# SW1106_100W_C_SH1.net
KiCad netlist of a schematic drawn in Altium Designer
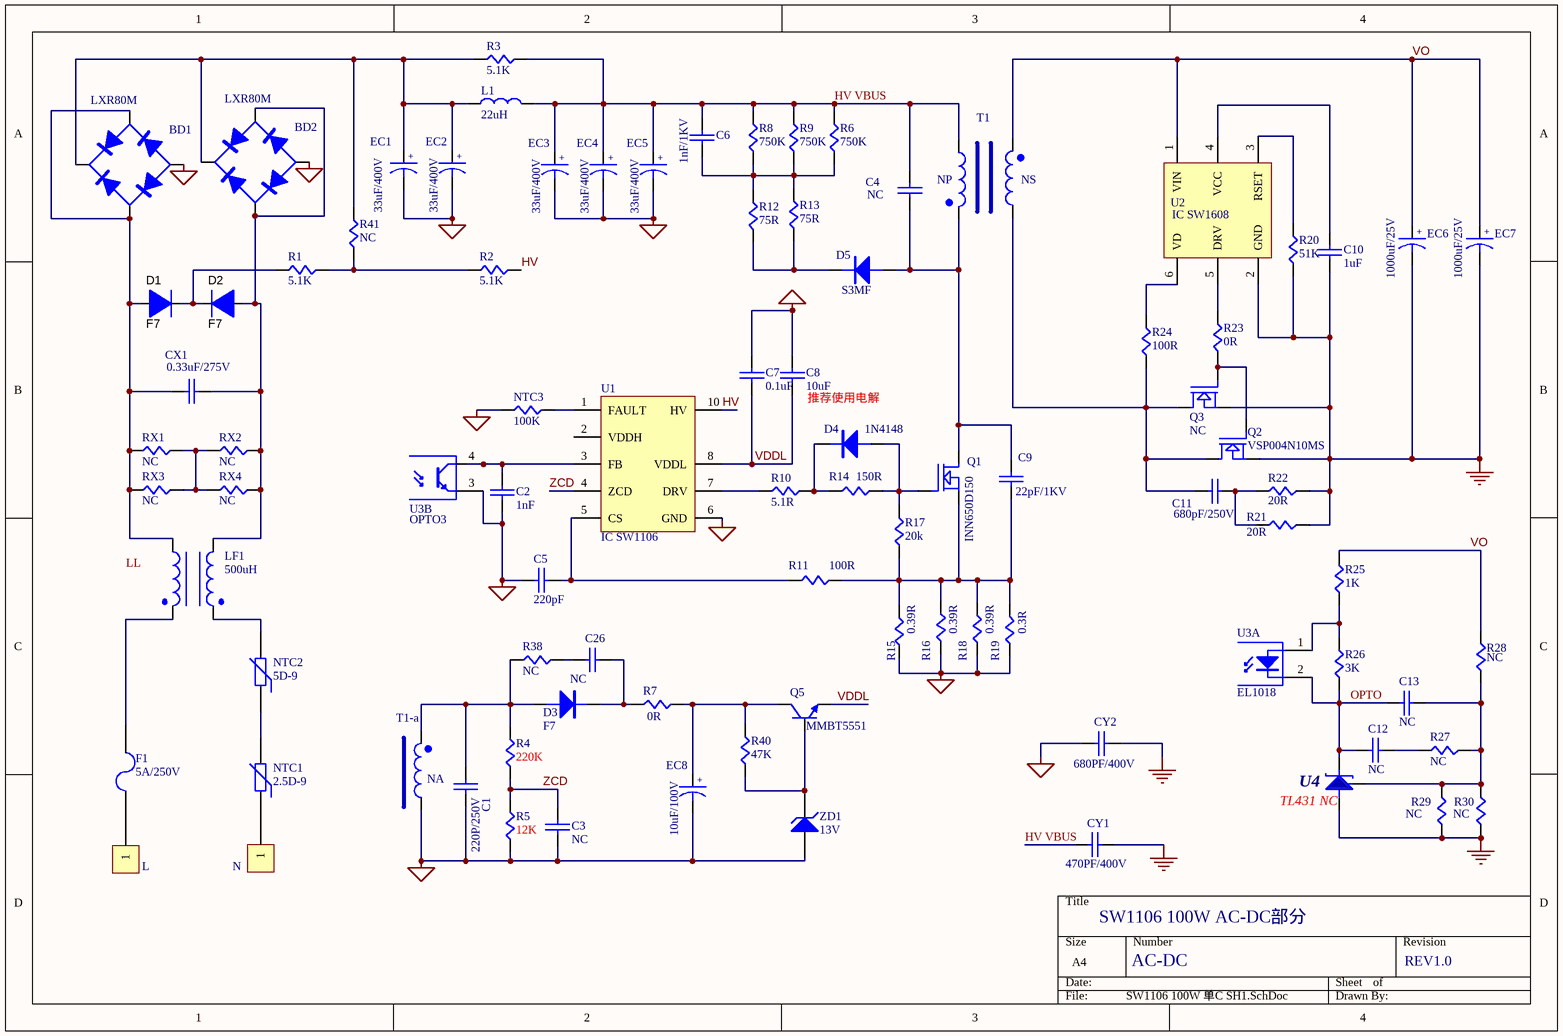
[diagram p0: SW1106 100W 单C SH1.SchDoc]

(export (version "E")
  (design (tool "Eeschema 10.0.6"))
  (components
    (comp (ref "BD1")
      (value "LXR80M")
      (footprint "BD-MBSL")
      (description "Diode")
      (libsource (lib "SCH-new") (part "BRIDGE"))
    )
    (comp (ref "BD2")
      (value "LXR80M")
      (footprint "BD-MBSL")
      (description "Diode")
      (libsource (lib "SCH-new") (part "BRIDGE"))
    )
    (comp (ref "C1")
      (value "220P/250V")
      (footprint "0603-C")
      (description "Capacitor")
      (libsource (lib "Backup of wdm_protel_libsch") (part "CAP"))
    )
    (comp (ref "C2")
      (value "1nF")
      (footprint "0603-C")
      (description "Capacitor")
      (libsource (lib "Backup of wdm_protel_libsch") (part "CAP"))
    )
    (comp (ref "C3")
      (value "NC")
      (footprint "0603-C")
      (description "Capacitor")
      (libsource (lib "Backup of wdm_protel_libsch") (part "CAP"))
    )
    (comp (ref "C4")
      (value "NC")
      (footprint "0805_C")
      (description "Capacitor")
      (libsource (lib "Backup of SC_ACDC_AD_libsch") (part "CAP"))
    )
    (comp (ref "C5")
      (value "220pF")
      (footprint "0603-C")
      (description "Capacitor")
      (libsource (lib "Backup of wdm_protel_libsch") (part "CAP"))
    )
    (comp (ref "C6")
      (value "1nF/1KV")
      (footprint "1206-C")
      (description "Capacitor")
      (libsource (lib "Backup of SC_ACDC_AD_libsch") (part "CAP"))
    )
    (comp (ref "C7")
      (value "0.1uF")
      (footprint "0805_C")
      (description "Capacitor")
      (libsource (lib "Backup of SC_ACDC_AD_libsch") (part "CAP"))
    )
    (comp (ref "C8")
      (value "10uF")
      (footprint "1206-C")
      (description "Capacitor")
      (libsource (lib "Backup of SC_ACDC_AD_libsch") (part "CAP"))
    )
    (comp (ref "C9")
      (value "22pF/1KV")
      (footprint "1206-C")
      (description "Capacitor")
      (libsource (lib "Backup of SC_ACDC_AD_libsch") (part "CAP"))
    )
    (comp (ref "C10")
      (value "1uF")
      (footprint "0603-C")
      (description "Capacitor")
      (libsource (lib "Backup of SC_ACDC_AD_libsch") (part "CAP"))
    )
    (comp (ref "C11")
      (value "680pF/250V")
      (footprint "0805_C")
      (description "Capacitor")
      (libsource (lib "Backup of SC_ACDC_AD_libsch") (part "CAP"))
    )
    (comp (ref "C12")
      (value "NC")
      (footprint "0603")
      (description "Capacitor")
      (libsource (lib "Backup of SC_ACDC_AD_libsch") (part "CAP"))
    )
    (comp (ref "C13")
      (value "NC")
      (footprint "0603")
      (description "Capacitor")
      (libsource (lib "Backup of SC_ACDC_AD_libsch") (part "CAP"))
    )
    (comp (ref "C26")
      (value "NC")
      (footprint "0805_C")
      (description "Capacitor")
      (libsource (lib "Backup of SC_ACDC_AD_libsch") (part "CAP"))
    )
    (comp (ref "CX1")
      (value "0.33uF/275V")
      (footprint "X-10-CAP - 3")
      (description "安规电容CHAMPION  X2\r\n尺寸：10X5X11mm（长X宽X高）\r\n脚距：7.5mm")
      (libsource (lib "xiaodenrui") (part "C"))
    )
    (comp (ref "CY1")
      (value "470PF/400V")
      (footprint "Y-SMD")
      (description "Capacitor")
      (libsource (lib "Backup of SC_ACDC_AD_libsch") (part "CAP"))
    )
    (comp (ref "CY2")
      (value "680PF/400V")
      (footprint "Y-SMD")
      (description "Capacitor")
      (libsource (lib "Backup of SC_ACDC_AD_libsch") (part "CAP"))
    )
    (comp (ref "D1")
      (value "F7")
      (footprint "SOD-123H")
      (description "1N4148 SOD323(0805)")
      (libsource (lib "*") (part "CSFMT108-HF"))
    )
    (comp (ref "D2")
      (value "F7")
      (footprint "SOD-123H")
      (description "1N4148 SOD323(0805)")
      (libsource (lib "*") (part "CSFMT108-HF"))
    )
    (comp (ref "D3")
      (value "F7")
      (footprint "SOD-123F")
      (description "Diode")
      (libsource (lib "Backup of wdm_protel_libsch") (part "DIODE_1"))
    )
    (comp (ref "D4")
      (value "1N4148")
      (footprint "SOD-323")
      (description "Diode")
      (libsource (lib "Backup of wdm_protel_libsch") (part "DIODE_1"))
    )
    (comp (ref "D5")
      (value "S3MF")
      (footprint "DIODE-S2MB")
      (description "Diode")
      (libsource (lib "Backup of SC_ACDC_AD_libsch") (part "DIODE"))
    )
    (comp (ref "EC1")
      (value "33uF/400V")
      (footprint "CD-8/3.5")
      (description "Capacitor")
      (libsource (lib "Backup of SC_ACDC_AD_libsch") (part "CAPACITOR POL"))
    )
    (comp (ref "EC2")
      (value "33uF/400V")
      (footprint "CD-8/3.5")
      (description "Capacitor")
      (libsource (lib "Backup of SC_ACDC_AD_libsch") (part "CAPACITOR POL"))
    )
    (comp (ref "EC3")
      (value "33uF/400V")
      (footprint "CD-8/3.5")
      (description "Capacitor")
      (libsource (lib "Backup of SC_ACDC_AD_libsch") (part "CAPACITOR POL"))
    )
    (comp (ref "EC4")
      (value "33uF/400V")
      (footprint "CD-8/3.5")
      (description "Capacitor")
      (libsource (lib "Backup of SC_ACDC_AD_libsch") (part "CAPACITOR POL"))
    )
    (comp (ref "EC5")
      (value "33uF/400V")
      (footprint "CD-8/3.5")
      (description "Capacitor")
      (libsource (lib "Backup of SC_ACDC_AD_libsch") (part "CAPACITOR POL"))
    )
    (comp (ref "EC6")
      (value "1000uF/25V")
      (footprint "CD-6.3/2.3")
      (description "Capacitor")
      (libsource (lib "Backup of SC_ACDC_AD_libsch") (part "CAPACITOR POL"))
    )
    (comp (ref "EC7")
      (value "1000uF/25V")
      (footprint "CD-6.3/2.3")
      (description "Capacitor")
      (libsource (lib "Backup of SC_ACDC_AD_libsch") (part "CAPACITOR POL"))
    )
    (comp (ref "EC8")
      (value "10uF/100V")
      (footprint "CD-8/3.5")
      (description "Capacitor")
      (libsource (lib "Backup of SC_ACDC_AD_libsch") (part "CAPACITOR POL"))
    )
    (comp (ref "F1")
      (value "5A/250V")
      (footprint "F-8.5*4-P5")
      (description "Fuse")
      (libsource (lib "Backup of SC_ACDC_AD_libsch") (part "FUSE"))
    )
    (comp (ref "L")
      (value "L")
      (footprint "焊盘1.5mm")
      (description "Connector")
      (libsource (lib "Backup of SC_ACDC_AD_libsch") (part "CON1"))
    )
    (comp (ref "L1")
      (value "22uH")
      (footprint "LF-D8-P5")
      (description "inductor")
      (libsource (lib "Backup of SC_ACDC_AD_libsch") (part "L1"))
    )
    (comp (ref "LF1")
      (value "500uH")
      (footprint "LF-9X3.2")
      (description "16.2uH")
      (libsource (lib "SCH-new") (part "LF-4-7"))
    )
    (comp (ref "N")
      (value "N")
      (footprint "焊盘1.5mm")
      (description "Connector")
      (libsource (lib "Backup of SC_ACDC_AD_libsch") (part "CON1"))
    )
    (comp (ref "NS") (value "~") (libsource (lib "*") (part "INDUCTOR")))
    (comp (ref "NTC1")
      (value "2.5D-9")
      (footprint "5D9")
      (description "Varistor (Voltage-Sensitive Resistor)")
      (fields (field (name "PUBLISHER") "Altium Limited"))
      (libsource (lib "Miscellaneous Devices") (part "Res Varistor"))
    )
    (comp (ref "NTC2")
      (value "5D-9")
      (footprint "5D9")
      (description "Varistor (Voltage-Sensitive Resistor)")
      (fields (field (name "PUBLISHER") "Altium Limited"))
      (libsource (lib "Miscellaneous Devices") (part "Res Varistor"))
    )
    (comp (ref "NTC3")
      (value "100K")
      (footprint "0603-R")
      (libsource (lib "Backup of SC_ACDC_AD_libsch") (part "RES2"))
    )
    (comp (ref "Q1")
      (value "INN650D150")
      (footprint "TO220-GDS")
      (description "SFS06R02UG 60V/3.2mR PDFN5*6 东微")
      (libsource (lib "zoujianSch-AD20-1.0") (part "NMOSFET (Z)"))
    )
    (comp (ref "Q2")
      (value "VSP004N10MS")
      (footprint "TO220-GDS")
      (description "SFS06R02UG 60V/3.2mR PDFN5*6 东微")
      (libsource (lib "zoujianSch-AD20-1.0") (part "NMOSFET (Z)"))
    )
    (comp (ref "Q3")
      (value "NC")
      (footprint "TO220-GDS")
      (description "SFS06R02UG 60V/3.2mR PDFN5*6 东微")
      (libsource (lib "zoujianSch-AD20-1.0") (part "NMOSFET (Z)"))
    )
    (comp (ref "Q5")
      (value "MMBT5551")
      (footprint "SOT-23")
      (description "NPN 三极管")
      (libsource (lib "元件库2020-10-13") (part "NPN"))
    )
    (comp (ref "R1")
      (value "5.1K")
      (footprint "1206-R")
      (libsource (lib "Backup of SC_ACDC_AD_libsch") (part "RES2"))
    )
    (comp (ref "R2")
      (value "5.1K")
      (footprint "1206-R")
      (libsource (lib "Backup of SC_ACDC_AD_libsch") (part "RES2"))
    )
    (comp (ref "R3")
      (value "5.1K")
      (footprint "1206-R")
      (libsource (lib "Backup of SC_ACDC_AD_libsch") (part "RES2"))
    )
    (comp (ref "R4")
      (value "220K")
      (footprint "0603-R")
      (libsource (lib "Backup of SC_ACDC_AD_libsch") (part "RES2"))
    )
    (comp (ref "R5")
      (value "12K")
      (footprint "0603-R")
      (libsource (lib "Backup of SC_ACDC_AD_libsch") (part "RES2"))
    )
    (comp (ref "R6")
      (value "750K")
      (footprint "1206-R")
      (libsource (lib "Backup of SC_ACDC_AD_libsch") (part "RES2"))
    )
    (comp (ref "R7")
      (value "0R")
      (footprint "0805-R")
      (libsource (lib "Backup of SC_ACDC_AD_libsch") (part "RES2"))
    )
    (comp (ref "R8")
      (value "750K")
      (footprint "1206-R")
      (libsource (lib "Backup of SC_ACDC_AD_libsch") (part "RES2"))
    )
    (comp (ref "R9")
      (value "750K")
      (footprint "1206-R")
      (libsource (lib "Backup of SC_ACDC_AD_libsch") (part "RES2"))
    )
    (comp (ref "R10")
      (value "5.1R")
      (footprint "0603-R")
      (libsource (lib "Backup of SC_ACDC_AD_libsch") (part "RES2"))
    )
    (comp (ref "R11")
      (value "100R")
      (footprint "0603-R")
      (libsource (lib "Backup of SC_ACDC_AD_libsch") (part "RES2"))
    )
    (comp (ref "R12")
      (value "75R")
      (footprint "1206-R")
      (libsource (lib "Backup of SC_ACDC_AD_libsch") (part "RES2"))
    )
    (comp (ref "R13")
      (value "75R")
      (footprint "1206-R")
      (libsource (lib "Backup of SC_ACDC_AD_libsch") (part "RES2"))
    )
    (comp (ref "R14")
      (value "150R")
      (footprint "0603-R")
      (libsource (lib "Backup of SC_ACDC_AD_libsch") (part "RES2"))
    )
    (comp (ref "R15")
      (value "0.39R")
      (footprint "1206-R")
      (libsource (lib "Backup of SC_ACDC_AD_libsch") (part "RES2"))
    )
    (comp (ref "R16")
      (value "0.39R")
      (footprint "1206-R")
      (libsource (lib "Backup of SC_ACDC_AD_libsch") (part "RES2"))
    )
    (comp (ref "R17")
      (value "20k")
      (footprint "0603-R")
      (libsource (lib "Backup of SC_ACDC_AD_libsch") (part "RES2"))
    )
    (comp (ref "R18")
      (value "0.39R")
      (footprint "1206-R")
      (libsource (lib "Backup of SC_ACDC_AD_libsch") (part "RES2"))
    )
    (comp (ref "R19")
      (value "0.3R")
      (footprint "1206-R")
      (libsource (lib "Backup of SC_ACDC_AD_libsch") (part "RES2"))
    )
    (comp (ref "R20")
      (value "51K")
      (footprint "0603-R")
      (libsource (lib "Backup of SC_ACDC_AD_libsch") (part "RES2"))
    )
    (comp (ref "R21")
      (value "20R")
      (footprint "0805-R")
      (libsource (lib "Backup of SC_ACDC_AD_libsch") (part "RES2"))
    )
    (comp (ref "R22")
      (value "20R")
      (footprint "0805-R")
      (libsource (lib "Backup of SC_ACDC_AD_libsch") (part "RES2"))
    )
    (comp (ref "R23")
      (value "0R")
      (footprint "0603-R")
      (libsource (lib "Backup of SC_ACDC_AD_libsch") (part "RES2"))
    )
    (comp (ref "R24")
      (value "100R")
      (footprint "0603-R")
      (libsource (lib "Backup of SC_ACDC_AD_libsch") (part "RES2"))
    )
    (comp (ref "R25")
      (value "1K")
      (footprint "0603-R")
      (libsource (lib "Backup of SC_ACDC_AD_libsch") (part "RES2"))
    )
    (comp (ref "R26")
      (value "3K")
      (footprint "0603-R")
      (libsource (lib "Backup of SC_ACDC_AD_libsch") (part "RES2"))
    )
    (comp (ref "R27")
      (value "NC")
      (footprint "0603")
      (libsource (lib "Backup of SC_ACDC_AD_libsch") (part "RES2"))
    )
    (comp (ref "R28")
      (value "NC")
      (footprint "0603")
      (libsource (lib "Backup of SC_ACDC_AD_libsch") (part "RES2"))
    )
    (comp (ref "R29")
      (value "NC")
      (footprint "0603")
      (libsource (lib "Backup of SC_ACDC_AD_libsch") (part "RES2"))
    )
    (comp (ref "R30")
      (value "NC")
      (footprint "0603")
      (libsource (lib "Backup of SC_ACDC_AD_libsch") (part "RES2"))
    )
    (comp (ref "R38")
      (value "NC")
      (footprint "0603-R")
      (libsource (lib "Backup of SC_ACDC_AD_libsch") (part "RES2"))
    )
    (comp (ref "R40")
      (value "47K")
      (footprint "0805-R")
      (libsource (lib "Backup of SC_ACDC_AD_libsch") (part "RES2"))
    )
    (comp (ref "R41")
      (value "NC")
      (footprint "1206-R")
      (libsource (lib "Backup of SC_ACDC_AD_libsch") (part "RES2"))
    )
    (comp (ref "RX1")
      (value "NC")
      (footprint "1206-R")
      (libsource (lib "Backup of SC_ACDC_AD_libsch") (part "RES2"))
    )
    (comp (ref "RX2")
      (value "NC")
      (footprint "1206-R")
      (libsource (lib "Backup of SC_ACDC_AD_libsch") (part "RES2"))
    )
    (comp (ref "RX3")
      (value "NC")
      (footprint "1206-R")
      (libsource (lib "Backup of SC_ACDC_AD_libsch") (part "RES2"))
    )
    (comp (ref "RX4")
      (value "NC")
      (footprint "1206-R")
      (libsource (lib "Backup of SC_ACDC_AD_libsch") (part "RES2"))
    )
    (comp (ref "T1") (value "NP") (libsource (lib "*") (part "INDUCTOR")))
    (comp (ref "T1-a") (value "NA") (libsource (lib "*") (part "INDUCTOR")))
    (comp (ref "U1") (value "IC SW1106") (libsource (lib "元件库2020-10-13") (part "IC SW1106")))
    (comp (ref "U2")
      (value "IC SW1608")
      (footprint "SOT23-6")
      (libsource (lib "元件库2020-10-13") (part "IC SW1608"))
    )
    (comp (ref "U3")
      (value "EL1018")
      (footprint "EL1019")
      (description "Optoisolator")
      (libsource (lib "") (part "OPTO3_1"))
    )
    (comp (ref "U4") (value "TL431 NC") (footprint "TL431") (libsource (lib "*") (part "IC431")))
    (comp (ref "ZD1")
      (value "13V")
      (footprint "DO-41")
      (description "稳压管")
      (libsource (lib "元件库2020-10-13") (part "D Zener"))
    )
  )
  (nets
    (net (code "1") (name "/HV") (class "Default")
      (node (ref "R2") (pin "2") (pinfunction "2_2") (pintype "passive"))
      (node (ref "U1") (pin "10") (pinfunction "HV_10") (pintype "passive"))
    )
    (net (code "2") (name "/HV VBUS") (class "Default")
      (node (ref "C4") (pin "1") (pinfunction "1_1") (pintype "passive"))
      (node (ref "C6") (pin "1") (pinfunction "1_1") (pintype "passive"))
      (node (ref "CY1") (pin "2") (pinfunction "2_2") (pintype "passive"))
      (node (ref "EC3") (pin "1") (pinfunction "1_1") (pintype "passive"))
      (node (ref "EC4") (pin "1") (pinfunction "1_1") (pintype "passive"))
      (node (ref "EC5") (pin "1") (pinfunction "1_1") (pintype "passive"))
      (node (ref "L1") (pin "1") (pintype "passive"))
      (node (ref "R3") (pin "1") (pinfunction "1_1") (pintype "passive"))
      (node (ref "R6") (pin "2") (pinfunction "2_2") (pintype "passive"))
      (node (ref "R8") (pin "2") (pinfunction "2_2") (pintype "passive"))
      (node (ref "R9") (pin "2") (pinfunction "2_2") (pintype "passive"))
      (node (ref "T1") (pin "1") (pinfunction "1_1") (pintype "passive"))
    )
    (net (code "4") (name "/OPTO") (class "Default")
      (node (ref "C12") (pin "2") (pinfunction "2_2") (pintype "passive"))
      (node (ref "C13") (pin "2") (pinfunction "2_2") (pintype "passive"))
      (node (ref "R26") (pin "2") (pinfunction "2_2") (pintype "passive"))
      (node (ref "U3") (pin "2") (pintype "passive"))
      (node (ref "U4") (pin "K") (pinfunction "K_K") (pintype "passive"))
    )
    (net (code "5") (name "/VDDL") (class "Default")
      (node (ref "C7") (pin "2") (pinfunction "2_2") (pintype "passive"))
      (node (ref "C8") (pin "1") (pinfunction "1_1") (pintype "passive"))
      (node (ref "Q5") (pin "3") (pinfunction "E_3") (pintype "passive"))
      (node (ref "U1") (pin "8") (pinfunction "VDDL_8") (pintype "passive"))
    )
    (net (code "6") (name "/VO") (class "Default")
      (node (ref "EC6") (pin "1") (pinfunction "1_1") (pintype "passive"))
      (node (ref "EC7") (pin "1") (pinfunction "1_1") (pintype "passive"))
      (node (ref "NS") (pin "2") (pinfunction "2_2") (pintype "passive"))
      (node (ref "R25") (pin "1") (pinfunction "1_1") (pintype "passive"))
      (node (ref "R28") (pin "2") (pinfunction "2_2") (pintype "passive"))
      (node (ref "U2") (pin "1") (pinfunction "VIN_1") (pintype "passive"))
    )
    (net (code "7") (name "/ZCD") (class "Default")
      (node (ref "C3") (pin "1") (pinfunction "1_1") (pintype "passive"))
      (node (ref "R4") (pin "2") (pinfunction "2_2") (pintype "passive"))
      (node (ref "R5") (pin "1") (pinfunction "1_1") (pintype "passive"))
      (node (ref "U1") (pin "4") (pinfunction "ZCD_4") (pintype "passive"))
    )
    (net (code "8") (name "GND") (class "Default")
      (node (ref "C10") (pin "2") (pinfunction "2_2") (pintype "passive"))
      (node (ref "CY1") (pin "1") (pinfunction "1_1") (pintype "passive"))
      (node (ref "CY2") (pin "1") (pinfunction "1_1") (pintype "passive"))
      (node (ref "EC6") (pin "2") (pinfunction "2_2") (pintype "passive"))
      (node (ref "EC7") (pin "2") (pinfunction "2_2") (pintype "passive"))
      (node (ref "Q2") (pin "S") (pintype "power_in"))
      (node (ref "Q3") (pin "S") (pintype "power_in"))
      (node (ref "R20") (pin "1") (pinfunction "1_1") (pintype "passive"))
      (node (ref "R21") (pin "1") (pinfunction "1_1") (pintype "passive"))
      (node (ref "R22") (pin "1") (pinfunction "1_1") (pintype "passive"))
      (node (ref "R29") (pin "2") (pinfunction "2_2") (pintype "passive"))
      (node (ref "R30") (pin "1") (pinfunction "1_1") (pintype "passive"))
      (node (ref "U2") (pin "2") (pinfunction "GND_2") (pintype "passive"))
      (node (ref "U4") (pin "A") (pinfunction "A_A") (pintype "passive"))
    )
    (net (code "9") (name "Net-(BD1-Pad1)") (class "Default")
      (node (ref "BD1") (pin "1") (pinfunction "1_1") (pintype "passive"))
      (node (ref "BD2") (pin "1") (pinfunction "1_1") (pintype "passive"))
      (node (ref "EC1") (pin "1") (pinfunction "1_1") (pintype "passive"))
      (node (ref "EC2") (pin "1") (pinfunction "1_1") (pintype "passive"))
      (node (ref "L1") (pin "2") (pintype "passive"))
      (node (ref "R3") (pin "2") (pinfunction "2_2") (pintype "passive"))
      (node (ref "R41") (pin "2") (pinfunction "2_2") (pintype "passive"))
    )
    (net (code "10") (name "Net-(C6-Pad2)") (class "Default")
      (node (ref "C6") (pin "2") (pinfunction "2_2") (pintype "passive"))
      (node (ref "R12") (pin "2") (pinfunction "2_2") (pintype "passive"))
      (node (ref "R13") (pin "2") (pinfunction "2_2") (pintype "passive"))
      (node (ref "R6") (pin "1") (pinfunction "1_1") (pintype "passive"))
      (node (ref "R8") (pin "1") (pinfunction "1_1") (pintype "passive"))
      (node (ref "R9") (pin "1") (pinfunction "1_1") (pintype "passive"))
    )
    (net (code "11") (name "Net-(C9-Pad2)") (class "Default")
      (node (ref "C9") (pin "2") (pinfunction "2_2") (pintype "passive"))
      (node (ref "Q1") (pin "S") (pintype "power_in"))
      (node (ref "R11") (pin "1") (pinfunction "1_1") (pintype "passive"))
      (node (ref "R15") (pin "2") (pinfunction "2_2") (pintype "passive"))
      (node (ref "R16") (pin "2") (pinfunction "2_2") (pintype "passive"))
      (node (ref "R17") (pin "2") (pinfunction "2_2") (pintype "passive"))
      (node (ref "R18") (pin "2") (pinfunction "2_2") (pintype "passive"))
      (node (ref "R19") (pin "2") (pinfunction "2_2") (pintype "passive"))
    )
    (net (code "12") (name "Net-(C11-Pad1)") (class "Default")
      (node (ref "C11") (pin "1") (pinfunction "1_1") (pintype "passive"))
      (node (ref "NS") (pin "1") (pinfunction "1_1") (pintype "passive"))
      (node (ref "Q2") (pin "D") (pintype "power_in"))
      (node (ref "Q3") (pin "D") (pintype "power_in"))
      (node (ref "R24") (pin "2") (pinfunction "2_2") (pintype "passive"))
    )
    (net (code "13") (name "Net-(C11-Pad2)") (class "Default")
      (node (ref "C11") (pin "2") (pinfunction "2_2") (pintype "passive"))
      (node (ref "R21") (pin "2") (pinfunction "2_2") (pintype "passive"))
      (node (ref "R22") (pin "2") (pinfunction "2_2") (pintype "passive"))
    )
    (net (code "14") (name "Net-(C12-Pad1)") (class "Default")
      (node (ref "C12") (pin "1") (pinfunction "1_1") (pintype "passive"))
      (node (ref "R27") (pin "1") (pinfunction "1_1") (pintype "passive"))
    )
    (net (code "15") (name "Net-(C13-Pad1)") (class "Default")
      (node (ref "C13") (pin "1") (pinfunction "1_1") (pintype "passive"))
      (node (ref "R27") (pin "2") (pinfunction "2_2") (pintype "passive"))
      (node (ref "R28") (pin "1") (pinfunction "1_1") (pintype "passive"))
      (node (ref "R29") (pin "1") (pinfunction "1_1") (pintype "passive"))
      (node (ref "R30") (pin "2") (pinfunction "2_2") (pintype "passive"))
      (node (ref "U4") (pin "R") (pinfunction "R_R") (pintype "passive"))
    )
    (net (code "16") (name "Net-(C26-Pad2)") (class "Default")
      (node (ref "C26") (pin "2") (pinfunction "2_2") (pintype "passive"))
      (node (ref "R38") (pin "2") (pinfunction "2_2") (pintype "passive"))
    )
    (net (code "17") (name "Net-(D1-A)") (class "Default")
      (node (ref "BD1") (pin "2") (pinfunction "2_2") (pintype "passive"))
      (node (ref "BD1") (pin "3") (pinfunction "3_3") (pintype "passive"))
      (node (ref "CX1") (pin "2") (pinfunction "2_2") (pintype "passive"))
      (node (ref "D1") (pin "2") (pinfunction "A_2") (pintype "passive"))
      (node (ref "LF1") (pin "3") (pinfunction "3_3") (pintype "passive"))
      (node (ref "RX1") (pin "1") (pinfunction "1_1") (pintype "passive"))
      (node (ref "RX3") (pin "1") (pinfunction "1_1") (pintype "passive"))
    )
    (net (code "18") (name "Net-(D1-K)") (class "Default")
      (node (ref "D1") (pin "1") (pinfunction "K_1") (pintype "passive"))
      (node (ref "D2") (pin "1") (pinfunction "K_1") (pintype "passive"))
      (node (ref "R1") (pin "1") (pinfunction "1_1") (pintype "passive"))
    )
    (net (code "19") (name "Net-(D2-A)") (class "Default")
      (node (ref "BD2") (pin "2") (pinfunction "2_2") (pintype "passive"))
      (node (ref "BD2") (pin "3") (pinfunction "3_3") (pintype "passive"))
      (node (ref "CX1") (pin "1") (pinfunction "1_1") (pintype "passive"))
      (node (ref "D2") (pin "2") (pinfunction "A_2") (pintype "passive"))
      (node (ref "LF1") (pin "4") (pinfunction "4_4") (pintype "passive"))
      (node (ref "RX2") (pin "2") (pinfunction "2_2") (pintype "passive"))
      (node (ref "RX4") (pin "2") (pinfunction "2_2") (pintype "passive"))
    )
    (net (code "20") (name "Net-(D3-A)") (class "Default")
      (node (ref "C1") (pin "1") (pinfunction "1_1") (pintype "passive"))
      (node (ref "D3") (pin "1") (pinfunction "A_1") (pintype "passive"))
      (node (ref "R38") (pin "1") (pinfunction "1_1") (pintype "passive"))
      (node (ref "R4") (pin "1") (pinfunction "1_1") (pintype "passive"))
      (node (ref "T1-a") (pin "2") (pinfunction "2_2") (pintype "passive"))
    )
    (net (code "21") (name "Net-(D3-K)") (class "Default")
      (node (ref "C26") (pin "1") (pinfunction "1_1") (pintype "passive"))
      (node (ref "D3") (pin "2") (pinfunction "K_2") (pintype "passive"))
      (node (ref "R7") (pin "1") (pinfunction "1_1") (pintype "passive"))
    )
    (net (code "22") (name "Net-(D4-A)") (class "Default")
      (node (ref "D4") (pin "1") (pinfunction "A_1") (pintype "passive"))
      (node (ref "Q1") (pin "G") (pintype "power_in"))
      (node (ref "R14") (pin "1") (pinfunction "1_1") (pintype "passive"))
      (node (ref "R17") (pin "1") (pinfunction "1_1") (pintype "passive"))
    )
    (net (code "23") (name "Net-(D4-K)") (class "Default")
      (node (ref "D4") (pin "2") (pinfunction "K_2") (pintype "passive"))
      (node (ref "R10") (pin "1") (pinfunction "1_1") (pintype "passive"))
      (node (ref "R14") (pin "2") (pinfunction "2_2") (pintype "passive"))
    )
    (net (code "24") (name "Net-(D5-A)") (class "Default")
      (node (ref "C4") (pin "2") (pinfunction "2_2") (pintype "passive"))
      (node (ref "C9") (pin "1") (pinfunction "1_1") (pintype "passive"))
      (node (ref "D5") (pin "1") (pinfunction "A_1") (pintype "passive"))
      (node (ref "Q1") (pin "D") (pintype "power_in"))
      (node (ref "T1") (pin "2") (pinfunction "2_2") (pintype "passive"))
    )
    (net (code "25") (name "Net-(D5-K)") (class "Default")
      (node (ref "D5") (pin "2") (pinfunction "K_2") (pintype "passive"))
      (node (ref "R12") (pin "1") (pinfunction "1_1") (pintype "passive"))
      (node (ref "R13") (pin "1") (pinfunction "1_1") (pintype "passive"))
    )
    (net (code "26") (name "Net-(F1-Pad1)") (class "Default")
      (node (ref "F1") (pin "1") (pinfunction "1_1") (pintype "passive"))
      (node (ref "LF1") (pin "2") (pinfunction "2_2") (pintype "passive"))
    )
    (net (code "27") (name "Net-(F1-Pad2)") (class "Default")
      (node (ref "F1") (pin "2") (pinfunction "2_2") (pintype "passive"))
      (node (ref "L") (pin "1") (pinfunction "1_1") (pintype "passive"))
    )
    (net (code "28") (name "Net-(LF1-Pad1)") (class "Default")
      (node (ref "LF1") (pin "1") (pinfunction "1_1") (pintype "passive"))
      (node (ref "NTC2") (pin "2") (pinfunction "2_2") (pintype "passive"))
    )
    (net (code "29") (name "Net-(N-Pad1)") (class "Default")
      (node (ref "N") (pin "1") (pinfunction "1_1") (pintype "passive"))
      (node (ref "NTC1") (pin "1") (pinfunction "1_1") (pintype "passive"))
    )
    (net (code "30") (name "Net-(NTC1-Pad2)") (class "Default")
      (node (ref "NTC1") (pin "2") (pinfunction "2_2") (pintype "passive"))
      (node (ref "NTC2") (pin "1") (pinfunction "1_1") (pintype "passive"))
    )
    (net (code "31") (name "Net-(Q2-PadG)") (class "Default")
      (node (ref "Q2") (pin "G") (pintype "power_in"))
      (node (ref "Q3") (pin "G") (pintype "power_in"))
      (node (ref "R23") (pin "2") (pinfunction "2_2") (pintype "passive"))
    )
    (net (code "32") (name "Net-(Q5-B)") (class "Default")
      (node (ref "Q5") (pin "1") (pinfunction "B_1") (pintype "passive"))
      (node (ref "R40") (pin "1") (pinfunction "1_1") (pintype "passive"))
      (node (ref "ZD1") (pin "2") (pinfunction "K_2") (pintype "passive"))
    )
    (net (code "33") (name "Net-(Q5-C)") (class "Default")
      (node (ref "EC8") (pin "1") (pinfunction "1_1") (pintype "passive"))
      (node (ref "Q5") (pin "2") (pinfunction "C_2") (pintype "passive"))
      (node (ref "R40") (pin "2") (pinfunction "2_2") (pintype "passive"))
      (node (ref "R7") (pin "2") (pinfunction "2_2") (pintype "passive"))
    )
    (net (code "34") (name "Net-(R1-Pad2)") (class "Default")
      (node (ref "R1") (pin "2") (pinfunction "2_2") (pintype "passive"))
      (node (ref "R2") (pin "1") (pinfunction "1_1") (pintype "passive"))
      (node (ref "R41") (pin "1") (pinfunction "1_1") (pintype "passive"))
    )
    (net (code "35") (name "Net-(R25-Pad2)") (class "Default")
      (node (ref "R25") (pin "2") (pinfunction "2_2") (pintype "passive"))
      (node (ref "R26") (pin "1") (pinfunction "1_1") (pintype "passive"))
      (node (ref "U3") (pin "1") (pintype "passive"))
    )
    (net (code "36") (name "Net-(RX1-Pad2)") (class "Default")
      (node (ref "RX1") (pin "2") (pinfunction "2_2") (pintype "passive"))
      (node (ref "RX2") (pin "1") (pinfunction "1_1") (pintype "passive"))
      (node (ref "RX3") (pin "2") (pinfunction "2_2") (pintype "passive"))
      (node (ref "RX4") (pin "1") (pinfunction "1_1") (pintype "passive"))
    )
    (net (code "37") (name "Net-(U1-CS)") (class "Default")
      (node (ref "C5") (pin "1") (pinfunction "1_1") (pintype "passive"))
      (node (ref "R11") (pin "2") (pinfunction "2_2") (pintype "passive"))
      (node (ref "U1") (pin "5") (pinfunction "CS_5") (pintype "passive"))
    )
    (net (code "38") (name "Net-(U1-DRV)") (class "Default")
      (node (ref "R10") (pin "2") (pinfunction "2_2") (pintype "passive"))
      (node (ref "U1") (pin "7") (pinfunction "DRV_7") (pintype "passive"))
    )
    (net (code "39") (name "Net-(U1-FAULT)") (class "Default")
      (node (ref "NTC3") (pin "1") (pinfunction "1_1") (pintype "passive"))
      (node (ref "U1") (pin "1") (pinfunction "FAULT_1") (pintype "passive"))
    )
    (net (code "40") (name "Net-(U1-FB)") (class "Default")
      (node (ref "C2") (pin "1") (pinfunction "1_1") (pintype "passive"))
      (node (ref "U1") (pin "3") (pinfunction "FB_3") (pintype "passive"))
      (node (ref "U3") (pin "4") (pintype "passive"))
    )
    (net (code "41") (name "Net-(U2-DRV)") (class "Default")
      (node (ref "R23") (pin "1") (pinfunction "1_1") (pintype "passive"))
      (node (ref "U2") (pin "5") (pinfunction "DRV_5") (pintype "passive"))
    )
    (net (code "42") (name "Net-(U2-RSET)") (class "Default")
      (node (ref "R20") (pin "2") (pinfunction "2_2") (pintype "passive"))
      (node (ref "U2") (pin "3") (pinfunction "RSET_3") (pintype "passive"))
    )
    (net (code "43") (name "Net-(U2-VCC)") (class "Default")
      (node (ref "C10") (pin "1") (pinfunction "1_1") (pintype "passive"))
      (node (ref "U2") (pin "4") (pinfunction "VCC_4") (pintype "passive"))
    )
    (net (code "44") (name "Net-(U2-VD)") (class "Default")
      (node (ref "R24") (pin "1") (pinfunction "1_1") (pintype "passive"))
      (node (ref "U2") (pin "6") (pinfunction "VD_6") (pintype "passive"))
    )
    (net (code "45") (name "PGND") (class "Default")
      (node (ref "BD1") (pin "4") (pinfunction "4_4") (pintype "passive"))
      (node (ref "BD2") (pin "4") (pinfunction "4_4") (pintype "passive"))
      (node (ref "C1") (pin "2") (pinfunction "2_2") (pintype "passive"))
      (node (ref "C2") (pin "2") (pinfunction "2_2") (pintype "passive"))
      (node (ref "C3") (pin "2") (pinfunction "2_2") (pintype "passive"))
      (node (ref "C5") (pin "2") (pinfunction "2_2") (pintype "passive"))
      (node (ref "C7") (pin "1") (pinfunction "1_1") (pintype "passive"))
      (node (ref "C8") (pin "2") (pinfunction "2_2") (pintype "passive"))
      (node (ref "CY2") (pin "2") (pinfunction "2_2") (pintype "passive"))
      (node (ref "EC1") (pin "2") (pinfunction "2_2") (pintype "passive"))
      (node (ref "EC2") (pin "2") (pinfunction "2_2") (pintype "passive"))
      (node (ref "EC3") (pin "2") (pinfunction "2_2") (pintype "passive"))
      (node (ref "EC4") (pin "2") (pinfunction "2_2") (pintype "passive"))
      (node (ref "EC5") (pin "2") (pinfunction "2_2") (pintype "passive"))
      (node (ref "EC8") (pin "2") (pinfunction "2_2") (pintype "passive"))
      (node (ref "NTC3") (pin "2") (pinfunction "2_2") (pintype "passive"))
      (node (ref "R15") (pin "1") (pinfunction "1_1") (pintype "passive"))
      (node (ref "R16") (pin "1") (pinfunction "1_1") (pintype "passive"))
      (node (ref "R18") (pin "1") (pinfunction "1_1") (pintype "passive"))
      (node (ref "R19") (pin "1") (pinfunction "1_1") (pintype "passive"))
      (node (ref "R5") (pin "2") (pinfunction "2_2") (pintype "passive"))
      (node (ref "T1-a") (pin "1") (pinfunction "1_1") (pintype "passive"))
      (node (ref "U1") (pin "6") (pinfunction "GND_6") (pintype "passive"))
      (node (ref "U3") (pin "3") (pintype "passive"))
      (node (ref "ZD1") (pin "1") (pinfunction "A_1") (pintype "passive"))
    )
    (net (code "46") (name "unconnected-(U1-VDDH-Pad2)") (class "Default")
      (node (ref "U1") (pin "2") (pinfunction "VDDH_2") (pintype "passive"))
    )
  )
)
